# AUDIO_INTERFACE.net
KiCad netlist of a schematic drawn in Altium Designer
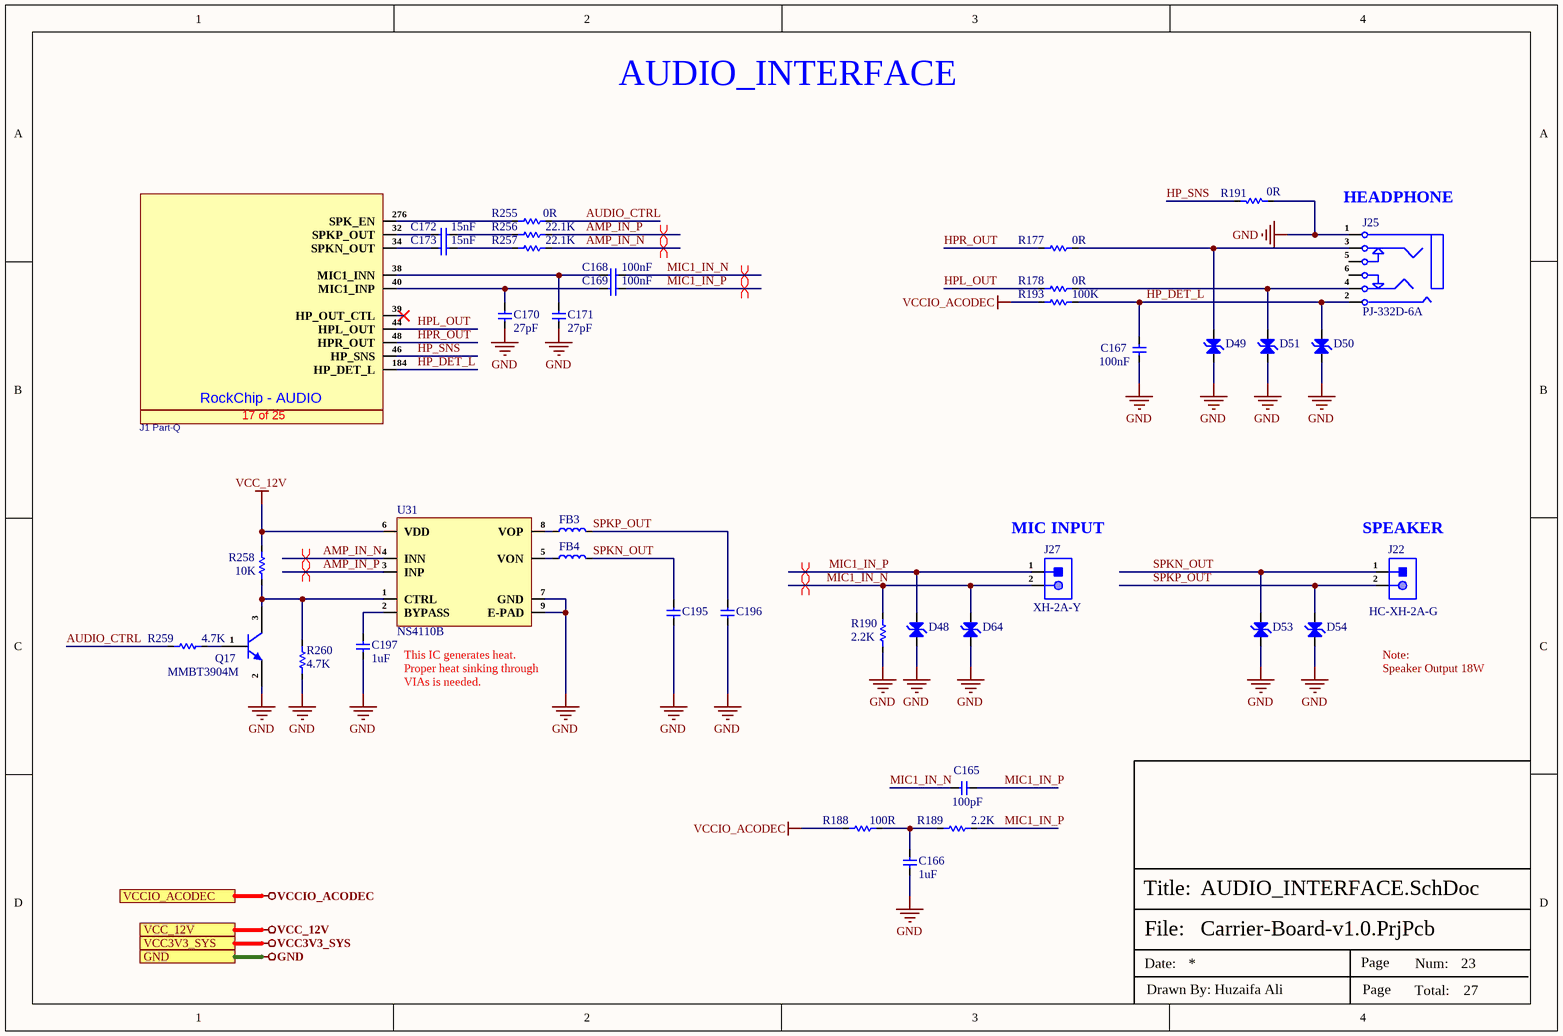
[diagram p0: AUDIO_INTERFACE.SchDoc]

(export (version "E")
  (design (tool "Eeschema 10.0.6"))
  (components
    (comp (ref "C165")
      (value "100pF")
      (footprint "Cap-0402")
      (description "CAP CER 100PF 50V C0G/NPO 0402")
      (fields
        (field (name "MANUFACTURER") "Yageo")
        (field (name "MANUFACTURER PART NUMBER") "CC0402JRNPO9BN101")
      )
      (libsource (lib "eSpark Libraries") (part "CC0402JRNPO9BN101"))
    )
    (comp (ref "C166")
      (value "1uF")
      (footprint "Cap-0402")
      (description "CAP CER 1UF 25V X5R 0402")
      (fields
        (field (name "MANUFACTURER") "Yageo")
        (field (name "MANUFACTURER PART NUMBER") "CC0402KRX5R8BB105")
      )
      (libsource (lib "eSpark Libraries") (part "CC0402KRX5R8BB105"))
    )
    (comp (ref "C167")
      (value "100nF")
      (footprint "Cap-0402")
      (description "CAP CER 0.1UF 16V X5R 0402")
      (fields
        (field (name "MANUFACTURER") "Yageo")
        (field (name "MANUFACTURER PART NUMBER") "CC0402KRX5R7BB104")
      )
      (libsource (lib "eSpark Libraries") (part "CC0402KRX5R7BB104"))
    )
    (comp (ref "C168")
      (value "100nF")
      (footprint "Cap-0402")
      (description "CAP CER 0.1UF 16V X5R 0402")
      (fields
        (field (name "MANUFACTURER") "Yageo")
        (field (name "MANUFACTURER PART NUMBER") "CC0402KRX5R7BB104")
      )
      (libsource (lib "eSpark Libraries") (part "CC0402KRX5R7BB104"))
    )
    (comp (ref "C169")
      (value "100nF")
      (footprint "Cap-0402")
      (description "CAP CER 0.1UF 16V X5R 0402")
      (fields
        (field (name "MANUFACTURER") "Yageo")
        (field (name "MANUFACTURER PART NUMBER") "CC0402KRX5R7BB104")
      )
      (libsource (lib "eSpark Libraries") (part "CC0402KRX5R7BB104"))
    )
    (comp (ref "C170")
      (value "27pF")
      (footprint "Cap-0402")
      (description "CAP CER 27PF 25V C0G/NP0 0402")
      (fields
        (field (name "MANUFACTURER") "Walsin Technologies")
        (field (name "MANUFACTURER PART NUMBER") "0402N270J250CT")
      )
      (libsource (lib "eSpark Libraries") (part "0402N270J250CT"))
    )
    (comp (ref "C171")
      (value "27pF")
      (footprint "Cap-0402")
      (description "CAP CER 27PF 25V C0G/NP0 0402")
      (fields
        (field (name "MANUFACTURER") "Walsin Technologies")
        (field (name "MANUFACTURER PART NUMBER") "0402N270J250CT")
      )
      (libsource (lib "eSpark Libraries") (part "0402N270J250CT"))
    )
    (comp (ref "C172")
      (value "15nF")
      (footprint "Cap-0402")
      (description "CAP CER 0.015UF 50V X7R 0402")
      (fields
        (field (name "MANUFACTURER") "Yageo")
        (field (name "MANUFACTURER PART NUMBER") "CC0402KRX7R9BB153")
      )
      (libsource (lib "eSpark Libraries") (part "CC0402KRX7R9BB153"))
    )
    (comp (ref "C173")
      (value "15nF")
      (footprint "Cap-0402")
      (description "CAP CER 0.015UF 50V X7R 0402")
      (fields
        (field (name "MANUFACTURER") "Yageo")
        (field (name "MANUFACTURER PART NUMBER") "CC0402KRX7R9BB153")
      )
      (libsource (lib "eSpark Libraries") (part "CC0402KRX7R9BB153"))
    )
    (comp (ref "C195")
      (value "~")
      (footprint "CAP-0603")
      (description "CAP CER 1000PF 25V C0G/NPO 0603")
      (fields
        (field (name "MANUFACTURER") "Yageo")
        (field (name "MANUFACTURER PART NUMBER") "CC0603JRNPO8BN102")
      )
      (libsource (lib "eSpark Libraries") (part "CC0603JRNPO8BN102"))
    )
    (comp (ref "C196")
      (value "~")
      (footprint "CAP-0603")
      (description "CAP CER 1000PF 25V C0G/NPO 0603")
      (fields
        (field (name "MANUFACTURER") "Yageo")
        (field (name "MANUFACTURER PART NUMBER") "CC0603JRNPO8BN102")
      )
      (libsource (lib "eSpark Libraries") (part "CC0603JRNPO8BN102"))
    )
    (comp (ref "C197")
      (value "1uF")
      (footprint "Cap-0603")
      (description "CAP CER 1UF 25V X5R 0603")
      (fields
        (field (name "MANUFACTURER") "Yageo")
        (field (name "MANUFACTURER PART NUMBER") "CC0603KRX5R8BB105")
      )
      (libsource (lib "eSpark Libraries") (part "CC0603KRX5R8BB105"))
    )
    (comp (ref "D48")
      (value "ESD5451N")
      (footprint "DFN1006-2L (Bi-Directional)")
      (description "DFN1006-2(0402) ESD Protection Devices ROHS")
      (fields (field (name "MANUFACTURER") "TECH PUBLIC") (field (name "LCSC PART NUMBER") "C2936977"))
      (libsource (lib "eSpark Libraries") (part "ESD5451N"))
    )
    (comp (ref "D49")
      (value "ESD5451N")
      (footprint "DFN1006-2L (Bi-Directional)")
      (description "DFN1006-2(0402) ESD Protection Devices ROHS")
      (fields (field (name "MANUFACTURER") "TECH PUBLIC") (field (name "LCSC PART NUMBER") "C2936977"))
      (libsource (lib "eSpark Libraries") (part "ESD5451N"))
    )
    (comp (ref "D50")
      (value "ESD5451N")
      (footprint "DFN1006-2L (Bi-Directional)")
      (description "DFN1006-2(0402) ESD Protection Devices ROHS")
      (fields (field (name "MANUFACTURER") "TECH PUBLIC") (field (name "LCSC PART NUMBER") "C2936977"))
      (libsource (lib "eSpark Libraries") (part "ESD5451N"))
    )
    (comp (ref "D51")
      (value "ESD5451N")
      (footprint "DFN1006-2L (Bi-Directional)")
      (description "DFN1006-2(0402) ESD Protection Devices ROHS")
      (fields (field (name "MANUFACTURER") "TECH PUBLIC") (field (name "LCSC PART NUMBER") "C2936977"))
      (libsource (lib "eSpark Libraries") (part "ESD5451N"))
    )
    (comp (ref "D53")
      (value "ESD5451N")
      (footprint "DFN1006-2L (Bi-Directional)")
      (description "DFN1006-2(0402) ESD Protection Devices ROHS")
      (fields (field (name "MANUFACTURER") "TECH PUBLIC") (field (name "LCSC PART NUMBER") "C2936977"))
      (libsource (lib "eSpark Libraries") (part "ESD5451N"))
    )
    (comp (ref "D54")
      (value "ESD5451N")
      (footprint "DFN1006-2L (Bi-Directional)")
      (description "DFN1006-2(0402) ESD Protection Devices ROHS")
      (fields (field (name "MANUFACTURER") "TECH PUBLIC") (field (name "LCSC PART NUMBER") "C2936977"))
      (libsource (lib "eSpark Libraries") (part "ESD5451N"))
    )
    (comp (ref "D64")
      (value "ESD5451N")
      (footprint "DFN1006-2L (Bi-Directional)")
      (description "DFN1006-2(0402) ESD Protection Devices ROHS")
      (fields (field (name "MANUFACTURER") "TECH PUBLIC") (field (name "LCSC PART NUMBER") "C2936977"))
      (libsource (lib "eSpark Libraries") (part "ESD5451N"))
    )
    (comp (ref "FB3")
      (value "~")
      (footprint "IND-1206")
      (description "FERRITE BEAD 1K OHM 1206 1LN")
      (fields
        (field (name "MANUFACTURER") "Murata")
        (field (name "MANUFACTURER PART NUMBER") "BLM31KN102SN1L")
      )
      (libsource (lib "eSpark Libraries") (part "BLM31KN102SN1L"))
    )
    (comp (ref "FB4")
      (value "~")
      (footprint "IND-1206")
      (description "FERRITE BEAD 1K OHM 1206 1LN")
      (fields
        (field (name "MANUFACTURER") "Murata")
        (field (name "MANUFACTURER PART NUMBER") "BLM31KN102SN1L")
      )
      (libsource (lib "eSpark Libraries") (part "BLM31KN102SN1L"))
    )
    (comp (ref "J1 Part-")
      (value "AS0B826-S78B-7H")
      (footprint "AS0B826-S78B-7H")
      (description "SMD,P=0.5mm,Surface Mount，Right Angle")
      (fields (field (name "MANUFACTURER") "FOXCONN") (field (name "LCSC PART NUMBER") "C426232"))
      (libsource (lib "Connector") (part "AS0B826-S78B-7H"))
    )
    (comp (ref "J22")
      (value "HC-XH-2A-G")
      (footprint "HC-XH-2A-G")
      (fields (field (name "MANUFACTURER") "HCTL") (field (name "LCSC PART NUMBER") "C5341201"))
      (libsource (lib "eSpark Libraries") (part "HC-XH-2A-G"))
    )
    (comp (ref "J25")
      (value "PJ-332D-6A")
      (footprint "PJ-332D-6A")
      (description "3.5mm headphone jack 1A SMD Audio Connectors ROHS")
      (fields
        (field (name "MANUFACTURER") "Korean Hroparts Elec")
        (field (name "LCSC PART NUMBER") "C840336")
      )
      (libsource (lib "eSpark Libraries") (part "PJ-332D-6A"))
    )
    (comp (ref "J27")
      (value "XH-2A-Y")
      (footprint "XH-2A-Y")
      (description "1x2P 2P XH 1 Tin 2.5mm 2 -25℃~+85℃ Brass 3A Straight Plugin,P=2.5mm Wire To Board Connector ROHS")
      (fields (field (name "MANUFACTURER") "HCTL") (field (name "LCSC PART NUMBER") "C2908595"))
      (libsource (lib "eSpark Libraries") (part "XH-2A-Y"))
    )
    (comp (ref "Q17")
      (value "MMBT3904M")
      (footprint "SOT-723")
      (fields (field (name "MANUFACTURER") "TECH PUBLIC") (field (name "LCSC PART NUMBER") "C2923360"))
      (libsource (lib "eSpark Libraries") (part "MMBT3904M"))
    )
    (comp (ref "R177")
      (value "0R")
      (footprint "Res-0402")
      (description "RES 0 OHM JUMPER 1/16W 0402")
      (fields
        (field (name "MANUFACTURER") "Yageo")
        (field (name "MANUFACTURER PART NUMBER") "RC0402FR-070RL")
      )
      (libsource (lib "eSpark Libraries") (part "RC0402FR-070RL"))
    )
    (comp (ref "R178")
      (value "0R")
      (footprint "Res-0402")
      (description "RES 0 OHM JUMPER 1/16W 0402")
      (fields
        (field (name "MANUFACTURER") "Yageo")
        (field (name "MANUFACTURER PART NUMBER") "RC0402FR-070RL")
      )
      (libsource (lib "eSpark Libraries") (part "RC0402FR-070RL"))
    )
    (comp (ref "R188")
      (value "100R")
      (footprint "Res-0402")
      (description "RES 100 OHM 1% 1/16W 0402")
      (fields
        (field (name "MANUFACTURER") "Yageo")
        (field (name "MANUFACTURER PART NUMBER") "RC0402FR-07100RL")
      )
      (libsource (lib "eSpark Libraries") (part "RC0402FR-07100RL"))
    )
    (comp (ref "R189")
      (value "2.2K")
      (footprint "Res-0402")
      (description "RES SMD 2.2K OHM 1% 1/16W 0402")
      (fields
        (field (name "MANUFACTURER") "Yageo")
        (field (name "MANUFACTURER PART NUMBER") "RC0402FR-072K2L")
      )
      (libsource (lib "eSpark Libraries") (part "RC0402FR-072K2L"))
    )
    (comp (ref "R190")
      (value "2.2K")
      (footprint "Res-0402")
      (description "RES SMD 2.2K OHM 1% 1/16W 0402")
      (fields
        (field (name "MANUFACTURER") "Yageo")
        (field (name "MANUFACTURER PART NUMBER") "RC0402FR-072K2L")
      )
      (libsource (lib "eSpark Libraries") (part "RC0402FR-072K2L"))
    )
    (comp (ref "R191")
      (value "0R")
      (footprint "Res-0402")
      (description "RES 0 OHM JUMPER 1/16W 0402")
      (fields
        (field (name "MANUFACTURER") "Yageo")
        (field (name "MANUFACTURER PART NUMBER") "RC0402FR-070RL")
      )
      (libsource (lib "eSpark Libraries") (part "RC0402FR-070RL"))
    )
    (comp (ref "R193")
      (value "100K")
      (footprint "Res-0402")
      (description "RES 100K OHM 1% 1/16W 0402")
      (fields
        (field (name "MANUFACTURER") "Yageo")
        (field (name "MANUFACTURER PART NUMBER") "RC0402FR-07100KL")
      )
      (libsource (lib "eSpark Libraries") (part "RC0402FR-07100KL"))
    )
    (comp (ref "R255")
      (value "0R")
      (footprint "Res-0402")
      (description "RES 0 OHM JUMPER 1/16W 0402")
      (fields
        (field (name "MANUFACTURER") "Yageo")
        (field (name "MANUFACTURER PART NUMBER") "RC0402FR-070RL")
      )
      (libsource (lib "eSpark Libraries") (part "RC0402FR-070RL"))
    )
    (comp (ref "R256")
      (value "22.1K")
      (footprint "Res-0402")
      (description "RES SMD 22.1KOHM 0.1% 1/16W 0402")
      (fields
        (field (name "MANUFACTURER") "Yageo")
        (field (name "MANUFACTURER PART NUMBER") "RT0402BRD0722K1L")
      )
      (libsource (lib "eSpark Libraries") (part "RT0402BRD0722K1L"))
    )
    (comp (ref "R257")
      (value "22.1K")
      (footprint "Res-0402")
      (description "RES SMD 22.1KOHM 0.1% 1/16W 0402")
      (fields
        (field (name "MANUFACTURER") "Yageo")
        (field (name "MANUFACTURER PART NUMBER") "RT0402BRD0722K1L")
      )
      (libsource (lib "eSpark Libraries") (part "RT0402BRD0722K1L"))
    )
    (comp (ref "R258")
      (value "10K")
      (footprint "Res-0402")
      (description "RES 10K OHM 1% 1/16W 0402")
      (fields
        (field (name "MANUFACTURER") "Yageo")
        (field (name "MANUFACTURER PART NUMBER") "RC0402FR-0710KL")
      )
      (libsource (lib "eSpark Libraries") (part "RC0402FR-0710KL"))
    )
    (comp (ref "R259")
      (value "4.7K")
      (footprint "Res-0402")
      (description "RES 4.7K OHM 1% 1/16W 0402")
      (fields
        (field (name "MANUFACTURER") "Yageo")
        (field (name "MANUFACTURER PART NUMBER") "RC0402FR-074K7L")
      )
      (libsource (lib "eSpark Libraries") (part "RC0402FR-074K7L"))
    )
    (comp (ref "R260")
      (value "4.7K")
      (footprint "Res-0402")
      (description "RES 4.7K OHM 1% 1/16W 0402")
      (fields
        (field (name "MANUFACTURER") "Yageo")
        (field (name "MANUFACTURER PART NUMBER") "RC0402FR-074K7L")
      )
      (libsource (lib "eSpark Libraries") (part "RC0402FR-074K7L"))
    )
    (comp (ref "U31")
      (value "NS4110B")
      (footprint "8-SOIC-EP")
      (description "SOP-8-EP Audio Power OpAmps ROHS")
      (fields
        (field (name "MANUFACTURER") "Shenzhen Nsiway Tech")
        (field (name "LCSC PART NUMBER") "C5334145")
      )
      (libsource (lib "eSpark Libraries") (part "NS4110B"))
    )
  )
  (nets
    (net (code "1") (name "/AMP_IN_N") (class "Default")
      (node (ref "R257") (pin "2") (pinfunction "2_2") (pintype "passive"))
      (node (ref "U31") (pin "4") (pinfunction "INN_4") (pintype "passive"))
    )
    (net (code "2") (name "/AMP_IN_P") (class "Default")
      (node (ref "R256") (pin "2") (pinfunction "2_2") (pintype "passive"))
      (node (ref "U31") (pin "3") (pinfunction "INP_3") (pintype "passive"))
    )
    (net (code "3") (name "/AUDIO_CTRL") (class "Default")
      (node (ref "R255") (pin "2") (pinfunction "2_2") (pintype "passive"))
      (node (ref "R259") (pin "1") (pinfunction "1_1") (pintype "passive"))
    )
    (net (code "4") (name "/HPL_OUT") (class "Default")
      (node (ref "J1 Part-") (pin "44") (pinfunction "HPL_OUT_44") (pintype "passive"))
      (node (ref "R178") (pin "1") (pinfunction "1_1") (pintype "passive"))
    )
    (net (code "5") (name "/HPR_OUT") (class "Default")
      (node (ref "J1 Part-") (pin "48") (pinfunction "HPR_OUT_48") (pintype "passive"))
      (node (ref "R177") (pin "1") (pinfunction "1_1") (pintype "passive"))
    )
    (net (code "6") (name "/HP_DET_L") (class "Default")
      (node (ref "C167") (pin "2") (pinfunction "2_2") (pintype "passive"))
      (node (ref "D50") (pin "2") (pinfunction "K_2") (pintype "passive"))
      (node (ref "J1 Part-") (pin "184") (pinfunction "HP_DET_L_184") (pintype "passive"))
      (node (ref "J25") (pin "2") (pinfunction "2_2") (pintype "passive"))
      (node (ref "R193") (pin "1") (pinfunction "1_1") (pintype "passive"))
    )
    (net (code "7") (name "/HP_SNS") (class "Default")
      (node (ref "J1 Part-") (pin "46") (pinfunction "HP_SNS_46") (pintype "passive"))
      (node (ref "R191") (pin "2") (pinfunction "2_2") (pintype "passive"))
    )
    (net (code "8") (name "/MIC1_IN_N") (class "Default")
      (node (ref "C165") (pin "2") (pinfunction "2_2") (pintype "passive"))
      (node (ref "C169") (pin "1") (pinfunction "1_1") (pintype "passive"))
      (node (ref "D64") (pin "2") (pinfunction "K_2") (pintype "passive"))
      (node (ref "J27") (pin "2") (pinfunction "2_2") (pintype "passive"))
      (node (ref "R190") (pin "2") (pinfunction "2_2") (pintype "passive"))
    )
    (net (code "9") (name "/MIC1_IN_P") (class "Default")
      (node (ref "C165") (pin "1") (pinfunction "1_1") (pintype "passive"))
      (node (ref "C168") (pin "1") (pinfunction "1_1") (pintype "passive"))
      (node (ref "D48") (pin "2") (pinfunction "K_2") (pintype "passive"))
      (node (ref "J27") (pin "1") (pinfunction "1_1") (pintype "passive"))
      (node (ref "R189") (pin "2") (pinfunction "2_2") (pintype "passive"))
    )
    (net (code "10") (name "/SPKN_OUT") (class "Default")
      (node (ref "C195") (pin "2") (pinfunction "2_2") (pintype "passive"))
      (node (ref "D53") (pin "2") (pinfunction "K_2") (pintype "passive"))
      (node (ref "FB4") (pin "2") (pinfunction "2_2") (pintype "passive"))
      (node (ref "J22") (pin "1") (pinfunction "1_1") (pintype "passive"))
    )
    (net (code "11") (name "/SPKP_OUT") (class "Default")
      (node (ref "C196") (pin "2") (pinfunction "2_2") (pintype "passive"))
      (node (ref "D54") (pin "2") (pinfunction "K_2") (pintype "passive"))
      (node (ref "FB3") (pin "2") (pinfunction "2_2") (pintype "passive"))
      (node (ref "J22") (pin "2") (pinfunction "2_2") (pintype "passive"))
    )
    (net (code "12") (name "GND") (class "Default")
      (node (ref "C166") (pin "1") (pinfunction "1_1") (pintype "passive"))
      (node (ref "C167") (pin "1") (pinfunction "1_1") (pintype "passive"))
      (node (ref "C170") (pin "1") (pinfunction "1_1") (pintype "passive"))
      (node (ref "C171") (pin "1") (pinfunction "1_1") (pintype "passive"))
      (node (ref "C195") (pin "1") (pinfunction "1_1") (pintype "passive"))
      (node (ref "C196") (pin "1") (pinfunction "1_1") (pintype "passive"))
      (node (ref "C197") (pin "1") (pinfunction "1_1") (pintype "passive"))
      (node (ref "D48") (pin "1") (pinfunction "K_1") (pintype "passive"))
      (node (ref "D49") (pin "1") (pinfunction "K_1") (pintype "passive"))
      (node (ref "D50") (pin "1") (pinfunction "K_1") (pintype "passive"))
      (node (ref "D51") (pin "1") (pinfunction "K_1") (pintype "passive"))
      (node (ref "D53") (pin "1") (pinfunction "K_1") (pintype "passive"))
      (node (ref "D54") (pin "1") (pinfunction "K_1") (pintype "passive"))
      (node (ref "D64") (pin "1") (pinfunction "K_1") (pintype "passive"))
      (node (ref "J25") (pin "1") (pinfunction "1_1") (pintype "passive"))
      (node (ref "Q17") (pin "2") (pinfunction "E_2") (pintype "passive"))
      (node (ref "R190") (pin "1") (pinfunction "1_1") (pintype "passive"))
      (node (ref "R191") (pin "1") (pinfunction "1_1") (pintype "passive"))
      (node (ref "R260") (pin "1") (pinfunction "1_1") (pintype "passive"))
      (node (ref "U31") (pin "7") (pinfunction "GND_7") (pintype "passive"))
      (node (ref "U31") (pin "9") (pinfunction "E-PAD_9") (pintype "passive"))
    )
    (net (code "13") (name "Net-(C166-Pad2)") (class "Default")
      (node (ref "C166") (pin "2") (pinfunction "2_2") (pintype "passive"))
      (node (ref "R188") (pin "2") (pinfunction "2_2") (pintype "passive"))
      (node (ref "R189") (pin "1") (pinfunction "1_1") (pintype "passive"))
    )
    (net (code "14") (name "Net-(C172-Pad2)") (class "Default")
      (node (ref "C172") (pin "2") (pinfunction "2_2") (pintype "passive"))
      (node (ref "R256") (pin "1") (pinfunction "1_1") (pintype "passive"))
    )
    (net (code "15") (name "Net-(C173-Pad2)") (class "Default")
      (node (ref "C173") (pin "2") (pinfunction "2_2") (pintype "passive"))
      (node (ref "R257") (pin "1") (pinfunction "1_1") (pintype "passive"))
    )
    (net (code "16") (name "Net-(D49-K-Pad2)") (class "Default")
      (node (ref "D49") (pin "2") (pinfunction "K_2") (pintype "passive"))
      (node (ref "J25") (pin "3") (pinfunction "3_3") (pintype "passive"))
      (node (ref "R177") (pin "2") (pinfunction "2_2") (pintype "passive"))
    )
    (net (code "17") (name "Net-(D51-K-Pad2)") (class "Default")
      (node (ref "D51") (pin "2") (pinfunction "K_2") (pintype "passive"))
      (node (ref "J25") (pin "4") (pinfunction "4_4") (pintype "passive"))
      (node (ref "R178") (pin "2") (pinfunction "2_2") (pintype "passive"))
    )
    (net (code "18") (name "Net-(J1 Part-Q-MIC1_INN)") (class "Default")
      (node (ref "C169") (pin "2") (pinfunction "2_2") (pintype "passive"))
      (node (ref "C171") (pin "2") (pinfunction "2_2") (pintype "passive"))
      (node (ref "J1 Part-") (pin "38") (pinfunction "MIC1_INN_38") (pintype "passive"))
    )
    (net (code "19") (name "Net-(J1 Part-Q-MIC1_INP)") (class "Default")
      (node (ref "C168") (pin "2") (pinfunction "2_2") (pintype "passive"))
      (node (ref "C170") (pin "2") (pinfunction "2_2") (pintype "passive"))
      (node (ref "J1 Part-") (pin "40") (pinfunction "MIC1_INP_40") (pintype "passive"))
    )
    (net (code "20") (name "Net-(J1 Part-Q-SPKN_OUT)") (class "Default")
      (node (ref "C173") (pin "1") (pinfunction "1_1") (pintype "passive"))
      (node (ref "J1 Part-") (pin "34") (pinfunction "SPKN_OUT_34") (pintype "passive"))
    )
    (net (code "21") (name "Net-(J1 Part-Q-SPKP_OUT)") (class "Default")
      (node (ref "C172") (pin "1") (pinfunction "1_1") (pintype "passive"))
      (node (ref "J1 Part-") (pin "32") (pinfunction "SPKP_OUT_32") (pintype "passive"))
    )
    (net (code "22") (name "Net-(J1 Part-Q-SPK_EN)") (class "Default")
      (node (ref "J1 Part-") (pin "276") (pinfunction "SPK_EN_276") (pintype "passive"))
      (node (ref "R255") (pin "1") (pinfunction "1_1") (pintype "passive"))
    )
    (net (code "23") (name "Net-(Q17-B)") (class "Default")
      (node (ref "Q17") (pin "1") (pinfunction "B_1") (pintype "passive"))
      (node (ref "R259") (pin "2") (pinfunction "2_2") (pintype "passive"))
    )
    (net (code "24") (name "Net-(Q17-C)") (class "Default")
      (node (ref "Q17") (pin "3") (pinfunction "C_3") (pintype "passive"))
      (node (ref "R258") (pin "1") (pinfunction "1_1") (pintype "passive"))
      (node (ref "R260") (pin "2") (pinfunction "2_2") (pintype "passive"))
      (node (ref "U31") (pin "1") (pinfunction "CTRL_1") (pintype "passive"))
    )
    (net (code "25") (name "Net-(U31-BYPASS)") (class "Default")
      (node (ref "C197") (pin "2") (pinfunction "2_2") (pintype "passive"))
      (node (ref "U31") (pin "2") (pinfunction "BYPASS_2") (pintype "passive"))
    )
    (net (code "26") (name "Net-(U31-VON)") (class "Default")
      (node (ref "FB4") (pin "1") (pinfunction "1_1") (pintype "passive"))
      (node (ref "U31") (pin "5") (pinfunction "VON_5") (pintype "passive"))
    )
    (net (code "27") (name "Net-(U31-VOP)") (class "Default")
      (node (ref "FB3") (pin "1") (pinfunction "1_1") (pintype "passive"))
      (node (ref "U31") (pin "8") (pinfunction "VOP_8") (pintype "passive"))
    )
    (net (code "29") (name "VCCIO_ACODEC") (class "Default")
      (node (ref "R188") (pin "1") (pinfunction "1_1") (pintype "passive"))
      (node (ref "R193") (pin "2") (pinfunction "2_2") (pintype "passive"))
    )
    (net (code "30") (name "VCC_12V") (class "Default")
      (node (ref "R258") (pin "2") (pinfunction "2_2") (pintype "passive"))
      (node (ref "U31") (pin "6") (pinfunction "VDD_6") (pintype "passive"))
    )
    (net (code "31") (name "unconnected-(J1 Part-Q-HP_OUT_CTL-Pad39)") (class "Default")
      (node (ref "J1 Part-") (pin "39") (pinfunction "HP_OUT_CTL_39") (pintype "passive+no_connect"))
    )
    (net (code "32") (name "unconnected-(J25-Pad5)") (class "Default")
      (node (ref "J25") (pin "5") (pinfunction "5_5") (pintype "passive"))
    )
    (net (code "33") (name "unconnected-(J25-Pad6)") (class "Default")
      (node (ref "J25") (pin "6") (pinfunction "6_6") (pintype "passive"))
    )
  )
)
